# MSP-RFID.net
KiCad netlist of a schematic drawn in Altium Designer
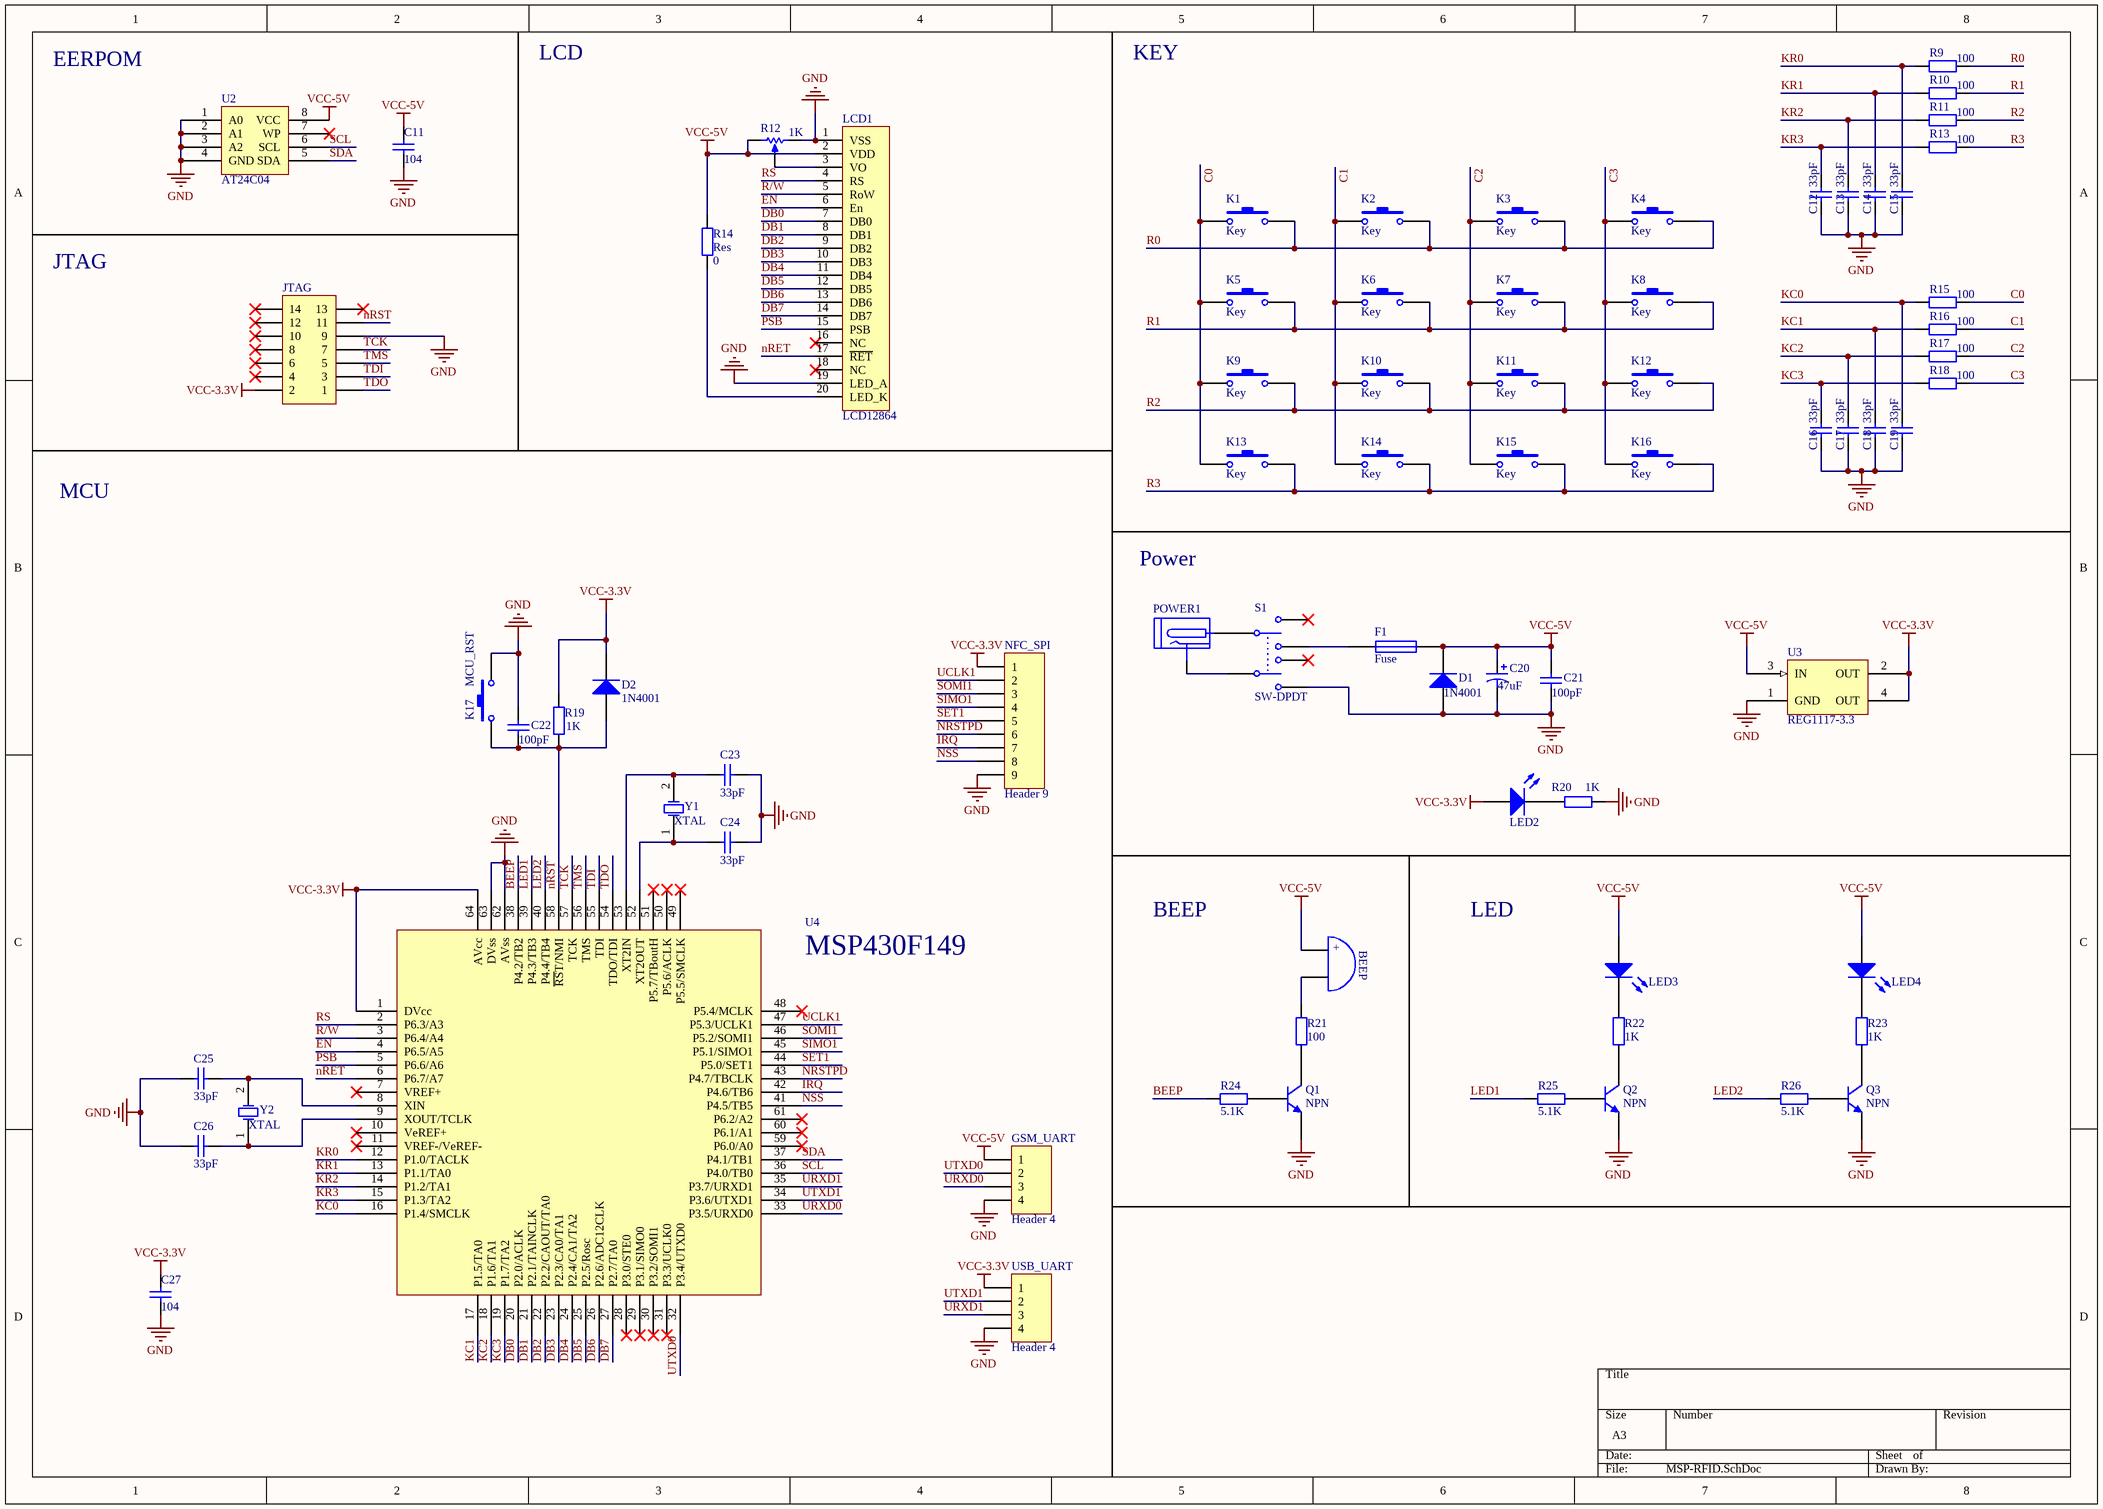
[diagram p0: MSP-RFID.SchDoc]

(export (version "E")
  (design (tool "Eeschema 10.0.6"))
  (components
    (comp (ref "BEEP1") (value "BEEP") (footprint "BEEP") (libsource (lib "common") (part "BEEP")))
    (comp (ref "C11")
      (value "104")
      (footprint "1608[0603]")
      (description "Capacitor")
      (fields (field (name "Comment") "Cap") (field (name "PUBLISHER") "Altium Limited"))
      (libsource (lib "common") (part "Cap"))
    )
    (comp (ref "C12")
      (value "33pF")
      (footprint "1608[0603]")
      (description "Capacitor")
      (fields (field (name "Comment") "Cap") (field (name "PUBLISHER") "Altium Limited"))
      (libsource (lib "common") (part "Cap"))
    )
    (comp (ref "C13")
      (value "33pF")
      (footprint "1608[0603]")
      (description "Capacitor")
      (fields (field (name "Comment") "Cap") (field (name "PUBLISHER") "Altium Limited"))
      (libsource (lib "common") (part "Cap"))
    )
    (comp (ref "C14")
      (value "33pF")
      (footprint "1608[0603]")
      (description "Capacitor")
      (fields (field (name "Comment") "Cap") (field (name "PUBLISHER") "Altium Limited"))
      (libsource (lib "common") (part "Cap"))
    )
    (comp (ref "C15")
      (value "33pF")
      (footprint "1608[0603]")
      (description "Capacitor")
      (fields (field (name "Comment") "Cap") (field (name "PUBLISHER") "Altium Limited"))
      (libsource (lib "common") (part "Cap"))
    )
    (comp (ref "C16")
      (value "33pF")
      (footprint "1608[0603]")
      (description "Capacitor")
      (fields (field (name "Comment") "Cap") (field (name "PUBLISHER") "Altium Limited"))
      (libsource (lib "common") (part "Cap"))
    )
    (comp (ref "C17")
      (value "33pF")
      (footprint "1608[0603]")
      (description "Capacitor")
      (fields (field (name "Comment") "Cap") (field (name "PUBLISHER") "Altium Limited"))
      (libsource (lib "common") (part "Cap"))
    )
    (comp (ref "C18")
      (value "33pF")
      (footprint "1608[0603]")
      (description "Capacitor")
      (fields (field (name "Comment") "Cap") (field (name "PUBLISHER") "Altium Limited"))
      (libsource (lib "common") (part "Cap"))
    )
    (comp (ref "C19")
      (value "33pF")
      (footprint "1608[0603]")
      (description "Capacitor")
      (fields (field (name "Comment") "Cap") (field (name "PUBLISHER") "Altium Limited"))
      (libsource (lib "common") (part "Cap"))
    )
    (comp (ref "C20")
      (value "47uF")
      (footprint "1608[0603] - POL")
      (description "Polarized Capacitor (Axial)")
      (fields (field (name "Comment") "CAP POL") (field (name "PUBLISHER") "Altium Limited"))
      (libsource (lib "common") (part "CAP POL"))
    )
    (comp (ref "C21")
      (value "100pF")
      (footprint "1608[0603]")
      (description "Capacitor")
      (fields (field (name "Comment") "Cap") (field (name "PUBLISHER") "Altium Limited"))
      (libsource (lib "common") (part "Cap"))
    )
    (comp (ref "C22")
      (value "100pF")
      (footprint "1608[0603]")
      (description "Capacitor")
      (fields (field (name "Comment") "Cap") (field (name "PUBLISHER") "Altium Limited"))
      (libsource (lib "common") (part "Cap"))
    )
    (comp (ref "C23")
      (value "33pF")
      (footprint "1608[0603]")
      (description "Capacitor")
      (fields (field (name "Comment") "Cap") (field (name "PUBLISHER") "Altium Limited"))
      (libsource (lib "common") (part "Cap"))
    )
    (comp (ref "C24")
      (value "33pF")
      (footprint "1608[0603]")
      (description "Capacitor")
      (fields (field (name "Comment") "Cap") (field (name "PUBLISHER") "Altium Limited"))
      (libsource (lib "common") (part "Cap"))
    )
    (comp (ref "C25")
      (value "33pF")
      (footprint "1608[0603]")
      (description "Capacitor")
      (fields (field (name "Comment") "Cap") (field (name "PUBLISHER") "Altium Limited"))
      (libsource (lib "common") (part "Cap"))
    )
    (comp (ref "C26")
      (value "33pF")
      (footprint "1608[0603]")
      (description "Capacitor")
      (fields (field (name "Comment") "Cap") (field (name "PUBLISHER") "Altium Limited"))
      (libsource (lib "common") (part "Cap"))
    )
    (comp (ref "C27")
      (value "104")
      (footprint "1608[0603]")
      (description "Capacitor")
      (fields (field (name "Comment") "Cap") (field (name "PUBLISHER") "Altium Limited"))
      (libsource (lib "common") (part "Cap"))
    )
    (comp (ref "D1")
      (value "1N4001")
      (footprint "1608[0603] - POL")
      (description "1 Amp General Purpose Rectifier")
      (fields (field (name "PUBLISHER") "Altium Limited"))
      (libsource (lib "common") (part "Diode 1N4001"))
    )
    (comp (ref "D2")
      (value "1N4001")
      (footprint "1608[0603] - POL")
      (description "1 Amp General Purpose Rectifier")
      (fields (field (name "PUBLISHER") "Altium Limited"))
      (libsource (lib "common") (part "Diode 1N4001"))
    )
    (comp (ref "F1") (value "Fuse") (footprint "1608[0603]") (libsource (lib "common") (part "FUSE1")))
    (comp (ref "GSM_UART")
      (value "Header 4")
      (footprint "HDR1X4")
      (description "Header, 4-Pin")
      (fields (field (name "PUBLISHER") "Altium Limited"))
      (libsource (lib "Miscellaneous Connectors") (part "Header 4"))
    )
    (comp (ref "JTAG")
      (value "Header 7X2H")
      (footprint "HDR2X7H")
      (description "Header, 7-Pin, Dual row, Right Angle")
      (fields (field (name "PUBLISHER") "Altium Limited"))
      (libsource (lib "Miscellaneous Connectors") (part "Header 7X2H"))
    )
    (comp (ref "K1") (value "Key") (footprint "Key-4") (libsource (lib "*") (part "SW-PB")))
    (comp (ref "K2") (value "Key") (footprint "Key-4") (libsource (lib "common") (part "SW-PB")))
    (comp (ref "K3") (value "Key") (footprint "Key-4") (libsource (lib "common") (part "SW-PB")))
    (comp (ref "K4") (value "Key") (footprint "Key-4") (libsource (lib "common") (part "SW-PB")))
    (comp (ref "K5") (value "Key") (footprint "Key-4") (libsource (lib "common") (part "SW-PB")))
    (comp (ref "K6") (value "Key") (footprint "Key-4") (libsource (lib "common") (part "SW-PB")))
    (comp (ref "K7") (value "Key") (footprint "Key-4") (libsource (lib "common") (part "SW-PB")))
    (comp (ref "K8") (value "Key") (footprint "Key-4") (libsource (lib "common") (part "SW-PB")))
    (comp (ref "K9") (value "Key") (footprint "Key-4") (libsource (lib "common") (part "SW-PB")))
    (comp (ref "K10") (value "Key") (footprint "Key-4") (libsource (lib "common") (part "SW-PB")))
    (comp (ref "K11") (value "Key") (footprint "Key-4") (libsource (lib "common") (part "SW-PB")))
    (comp (ref "K12") (value "Key") (footprint "Key-4") (libsource (lib "common") (part "SW-PB")))
    (comp (ref "K13") (value "Key") (footprint "Key-4") (libsource (lib "common") (part "SW-PB")))
    (comp (ref "K14") (value "Key") (footprint "Key-4") (libsource (lib "common") (part "SW-PB")))
    (comp (ref "K15") (value "Key") (footprint "Key-4") (libsource (lib "common") (part "SW-PB")))
    (comp (ref "K16") (value "Key") (footprint "Key-4") (libsource (lib "common") (part "SW-PB")))
    (comp (ref "K17") (value "MCU_RST") (footprint "Key-4") (libsource (lib "common") (part "SW-PB")))
    (comp (ref "LCD1") (value "LCD12864") (footprint "LCD-20PIN") (libsource (lib "*") (part "LCD12864")))
    (comp (ref "LED2") (value "LED") (footprint "2012[0805] - POL") (libsource (lib "common") (part "LED")))
    (comp (ref "LED3") (value "LED") (footprint "1608[0603] - POL") (libsource (lib "common") (part "LED")))
    (comp (ref "LED4") (value "LED") (footprint "1608[0603] - POL") (libsource (lib "common") (part "LED")))
    (comp (ref "NFC_SPI")
      (value "Header 9")
      (footprint "HDR1X9")
      (description "Header, 9-Pin")
      (fields (field (name "PUBLISHER") "Altium Limited"))
      (libsource (lib "Miscellaneous Connectors") (part "Header 9"))
    )
    (comp (ref "POWER1") (value "POWER") (footprint "POWER") (libsource (lib "51ExpBoard") (part "POWER")))
    (comp (ref "Q1") (value "NPN") (footprint "SOT23-3L") (libsource (lib "common") (part "NPN")))
    (comp (ref "Q2") (value "NPN") (footprint "SOT23-3L") (libsource (lib "common") (part "NPN")))
    (comp (ref "Q3") (value "NPN") (footprint "SOT23-3L") (libsource (lib "common") (part "NPN")))
    (comp (ref "R9")
      (value "100")
      (footprint "1608[0603]")
      (description "Resistor")
      (fields (field (name "Comment") "RES") (field (name "PUBLISHER") "Altium Limited"))
      (libsource (lib "common") (part "RES"))
    )
    (comp (ref "R10")
      (value "100")
      (footprint "1608[0603]")
      (description "Resistor")
      (fields (field (name "Comment") "RES") (field (name "PUBLISHER") "Altium Limited"))
      (libsource (lib "common") (part "RES"))
    )
    (comp (ref "R11")
      (value "100")
      (footprint "1608[0603]")
      (description "Resistor")
      (fields (field (name "Comment") "RES") (field (name "PUBLISHER") "Altium Limited"))
      (libsource (lib "common") (part "RES"))
    )
    (comp (ref "R12")
      (value "1K")
      (footprint "VR5")
      (description "Potentiometer")
      (fields (field (name "Comment") "RPot") (field (name "PUBLISHER") "Altium Limited"))
      (libsource (lib "Miscellaneous Devices") (part "RPot"))
    )
    (comp (ref "R13")
      (value "100")
      (footprint "1608[0603]")
      (description "Resistor")
      (fields (field (name "Comment") "RES") (field (name "PUBLISHER") "Altium Limited"))
      (libsource (lib "common") (part "RES"))
    )
    (comp (ref "R14")
      (value "Res")
      (footprint "1608[0603]")
      (description "Resistor")
      (fields (field (name "ALTIUM_VALUE") "0") (field (name "PUBLISHER") "Altium Limited"))
      (libsource (lib "*") (part "RES"))
    )
    (comp (ref "R15")
      (value "100")
      (footprint "1608[0603]")
      (description "Resistor")
      (fields (field (name "Comment") "RES") (field (name "PUBLISHER") "Altium Limited"))
      (libsource (lib "common") (part "RES"))
    )
    (comp (ref "R16")
      (value "100")
      (footprint "1608[0603]")
      (description "Resistor")
      (fields (field (name "Comment") "RES") (field (name "PUBLISHER") "Altium Limited"))
      (libsource (lib "common") (part "RES"))
    )
    (comp (ref "R17")
      (value "100")
      (footprint "1608[0603]")
      (description "Resistor")
      (fields (field (name "Comment") "RES") (field (name "PUBLISHER") "Altium Limited"))
      (libsource (lib "common") (part "RES"))
    )
    (comp (ref "R18")
      (value "100")
      (footprint "1608[0603]")
      (description "Resistor")
      (fields (field (name "Comment") "RES") (field (name "PUBLISHER") "Altium Limited"))
      (libsource (lib "common") (part "RES"))
    )
    (comp (ref "R19")
      (value "1K")
      (footprint "1608[0603]")
      (description "Resistor")
      (fields (field (name "Comment") "Res") (field (name "PUBLISHER") "Altium Limited"))
      (libsource (lib "") (part "RES_2"))
    )
    (comp (ref "R20")
      (value "1K")
      (footprint "1608[0603]")
      (description "Resistor")
      (fields (field (name "Comment") "Res") (field (name "PUBLISHER") "Altium Limited"))
      (libsource (lib "common") (part "RES"))
    )
    (comp (ref "R21")
      (value "100")
      (footprint "1608[0603]")
      (description "Resistor")
      (fields (field (name "Comment") "Res") (field (name "PUBLISHER") "Altium Limited"))
      (libsource (lib "") (part "RES_1"))
    )
    (comp (ref "R22")
      (value "1K")
      (footprint "1608[0603]")
      (description "Resistor")
      (fields (field (name "Comment") "Res") (field (name "PUBLISHER") "Altium Limited"))
      (libsource (lib "") (part "RES_1"))
    )
    (comp (ref "R23")
      (value "1K")
      (footprint "1608[0603]")
      (description "Resistor")
      (fields (field (name "Comment") "Res") (field (name "PUBLISHER") "Altium Limited"))
      (libsource (lib "") (part "RES_1"))
    )
    (comp (ref "R24")
      (value "5.1K")
      (footprint "1608[0603]")
      (description "Resistor")
      (fields (field (name "Comment") "Res") (field (name "PUBLISHER") "Altium Limited"))
      (libsource (lib "common") (part "RES"))
    )
    (comp (ref "R25")
      (value "5.1K")
      (footprint "1608[0603]")
      (description "Resistor")
      (fields (field (name "Comment") "Res") (field (name "PUBLISHER") "Altium Limited"))
      (libsource (lib "common") (part "RES"))
    )
    (comp (ref "R26")
      (value "5.1K")
      (footprint "1608[0603]")
      (description "Resistor")
      (fields (field (name "Comment") "Res") (field (name "PUBLISHER") "Altium Limited"))
      (libsource (lib "common") (part "RES"))
    )
    (comp (ref "S1")
      (value "SW-DPDT")
      (footprint "DPDT-6")
      (description "Double-Pole, Double-Throw Switch")
      (fields (field (name "PUBLISHER") "Altium Limited"))
      (libsource (lib "Miscellaneous Devices") (part "SW-DPDT"))
    )
    (comp (ref "U2")
      (value "AT24C04")
      (footprint "SOIC127P600-8AN")
      (libsource (lib "common") (part "AT24C04"))
    )
    (comp (ref "U3")
      (value "REG1117-3.3")
      (footprint "SOT223")
      (libsource (lib "MYSELF") (part "REG1117-3.3"))
    )
    (comp (ref "U4")
      (value "MSP430F149")
      (footprint "SQFP50P1200X1200-64N")
      (libsource (lib "msp430flash系列") (part "F14X"))
    )
    (comp (ref "USB_UART")
      (value "Header 4")
      (footprint "HDR1X4")
      (description "Header, 4-Pin")
      (fields (field (name "PUBLISHER") "Altium Limited"))
      (libsource (lib "Miscellaneous Connectors") (part "Header 4"))
    )
    (comp (ref "Y1")
      (value "XTAL")
      (footprint "XTAL")
      (description "Crystal Oscillator")
      (fields (field (name "PUBLISHER") "Altium Limited"))
      (libsource (lib "common") (part "XTAL"))
    )
    (comp (ref "Y2")
      (value "XTAL")
      (footprint "XTAL")
      (description "Crystal Oscillator")
      (fields (field (name "PUBLISHER") "Altium Limited"))
      (libsource (lib "common") (part "XTAL"))
    )
  )
  (nets
    (net (code "1") (name "/BEEP") (class "Default")
      (node (ref "R24") (pin "1") (pinfunction "1_1") (pintype "passive"))
      (node (ref "U4") (pin "38") (pinfunction "P4.2/TB2_38") (pintype "power_in"))
    )
    (net (code "2") (name "/C0") (class "Default")
      (node (ref "K1") (pin "1") (pinfunction "1_1") (pintype "passive"))
      (node (ref "K13") (pin "1") (pinfunction "1_1") (pintype "passive"))
      (node (ref "K5") (pin "1") (pinfunction "1_1") (pintype "passive"))
      (node (ref "K9") (pin "1") (pinfunction "1_1") (pintype "passive"))
      (node (ref "R15") (pin "2") (pinfunction "2_2") (pintype "passive"))
    )
    (net (code "3") (name "/C1") (class "Default")
      (node (ref "K10") (pin "1") (pinfunction "1_1") (pintype "passive"))
      (node (ref "K14") (pin "1") (pinfunction "1_1") (pintype "passive"))
      (node (ref "K2") (pin "1") (pinfunction "1_1") (pintype "passive"))
      (node (ref "K6") (pin "1") (pinfunction "1_1") (pintype "passive"))
      (node (ref "R16") (pin "2") (pinfunction "2_2") (pintype "passive"))
    )
    (net (code "4") (name "/C2") (class "Default")
      (node (ref "K11") (pin "1") (pinfunction "1_1") (pintype "passive"))
      (node (ref "K15") (pin "1") (pinfunction "1_1") (pintype "passive"))
      (node (ref "K3") (pin "1") (pinfunction "1_1") (pintype "passive"))
      (node (ref "K7") (pin "1") (pinfunction "1_1") (pintype "passive"))
      (node (ref "R17") (pin "2") (pinfunction "2_2") (pintype "passive"))
    )
    (net (code "5") (name "/C3") (class "Default")
      (node (ref "K12") (pin "1") (pinfunction "1_1") (pintype "passive"))
      (node (ref "K16") (pin "1") (pinfunction "1_1") (pintype "passive"))
      (node (ref "K4") (pin "1") (pinfunction "1_1") (pintype "passive"))
      (node (ref "K8") (pin "1") (pinfunction "1_1") (pintype "passive"))
      (node (ref "R18") (pin "2") (pinfunction "2_2") (pintype "passive"))
    )
    (net (code "6") (name "/DB0") (class "Default")
      (node (ref "LCD1") (pin "7") (pinfunction "DB0_7") (pintype "passive"))
      (node (ref "U4") (pin "20") (pinfunction "P2.0/ACLK_20") (pintype "power_in"))
    )
    (net (code "7") (name "/DB1") (class "Default")
      (node (ref "LCD1") (pin "8") (pinfunction "DB1_8") (pintype "passive"))
      (node (ref "U4") (pin "21") (pinfunction "P2.1/TAINCLK_21") (pintype "power_in"))
    )
    (net (code "8") (name "/DB2") (class "Default")
      (node (ref "LCD1") (pin "9") (pinfunction "DB2_9") (pintype "passive"))
      (node (ref "U4") (pin "22") (pinfunction "P2.2/CAOUT/TA0_22") (pintype "power_in"))
    )
    (net (code "9") (name "/DB3") (class "Default")
      (node (ref "LCD1") (pin "10") (pinfunction "DB3_10") (pintype "passive"))
      (node (ref "U4") (pin "23") (pinfunction "P2.3/CA0/TA1_23") (pintype "power_in"))
    )
    (net (code "10") (name "/DB4") (class "Default")
      (node (ref "LCD1") (pin "11") (pinfunction "DB4_11") (pintype "passive"))
      (node (ref "U4") (pin "24") (pinfunction "P2.4/CA1/TA2_24") (pintype "power_in"))
    )
    (net (code "11") (name "/DB5") (class "Default")
      (node (ref "LCD1") (pin "12") (pinfunction "DB5_12") (pintype "passive"))
      (node (ref "U4") (pin "25") (pinfunction "P2.5/Rosc_25") (pintype "power_in"))
    )
    (net (code "12") (name "/DB6") (class "Default")
      (node (ref "LCD1") (pin "13") (pinfunction "DB6_13") (pintype "passive"))
      (node (ref "U4") (pin "26") (pinfunction "P2.6/ADC12CLK_26") (pintype "power_in"))
    )
    (net (code "13") (name "/DB7") (class "Default")
      (node (ref "LCD1") (pin "14") (pinfunction "DB7_14") (pintype "passive"))
      (node (ref "U4") (pin "27") (pinfunction "P2.7/TA0_27") (pintype "power_in"))
    )
    (net (code "14") (name "/EN") (class "Default")
      (node (ref "LCD1") (pin "6") (pinfunction "En_6") (pintype "passive"))
      (node (ref "U4") (pin "4") (pinfunction "P6.5/A5_4") (pintype "power_in"))
    )
    (net (code "15") (name "/IRQ") (class "Default")
      (node (ref "NFC_SPI") (pin "7") (pinfunction "7_7") (pintype "passive"))
      (node (ref "U4") (pin "42") (pinfunction "P4.6/TB6_42") (pintype "power_in"))
    )
    (net (code "16") (name "/KC0") (class "Default")
      (node (ref "C19") (pin "1") (pinfunction "1_1") (pintype "passive"))
      (node (ref "R15") (pin "1") (pinfunction "1_1") (pintype "passive"))
      (node (ref "U4") (pin "16") (pinfunction "P1.4/SMCLK_16") (pintype "power_in"))
    )
    (net (code "17") (name "/KC1") (class "Default")
      (node (ref "C18") (pin "1") (pinfunction "1_1") (pintype "passive"))
      (node (ref "R16") (pin "1") (pinfunction "1_1") (pintype "passive"))
      (node (ref "U4") (pin "17") (pinfunction "P1.5/TA0_17") (pintype "power_in"))
    )
    (net (code "18") (name "/KC2") (class "Default")
      (node (ref "C17") (pin "1") (pinfunction "1_1") (pintype "passive"))
      (node (ref "R17") (pin "1") (pinfunction "1_1") (pintype "passive"))
      (node (ref "U4") (pin "18") (pinfunction "P1.6/TA1_18") (pintype "power_in"))
    )
    (net (code "19") (name "/KC3") (class "Default")
      (node (ref "C16") (pin "1") (pinfunction "1_1") (pintype "passive"))
      (node (ref "R18") (pin "1") (pinfunction "1_1") (pintype "passive"))
      (node (ref "U4") (pin "19") (pinfunction "P1.7/TA2_19") (pintype "power_in"))
    )
    (net (code "20") (name "/KR0") (class "Default")
      (node (ref "C15") (pin "1") (pinfunction "1_1") (pintype "passive"))
      (node (ref "R9") (pin "1") (pinfunction "1_1") (pintype "passive"))
      (node (ref "U4") (pin "12") (pinfunction "P1.0/TACLK_12") (pintype "power_in"))
    )
    (net (code "21") (name "/KR1") (class "Default")
      (node (ref "C14") (pin "1") (pinfunction "1_1") (pintype "passive"))
      (node (ref "R10") (pin "1") (pinfunction "1_1") (pintype "passive"))
      (node (ref "U4") (pin "13") (pinfunction "P1.1/TA0_13") (pintype "power_in"))
    )
    (net (code "22") (name "/KR2") (class "Default")
      (node (ref "C13") (pin "1") (pinfunction "1_1") (pintype "passive"))
      (node (ref "R11") (pin "1") (pinfunction "1_1") (pintype "passive"))
      (node (ref "U4") (pin "14") (pinfunction "P1.2/TA1_14") (pintype "power_in"))
    )
    (net (code "23") (name "/KR3") (class "Default")
      (node (ref "C12") (pin "1") (pinfunction "1_1") (pintype "passive"))
      (node (ref "R13") (pin "1") (pinfunction "1_1") (pintype "passive"))
      (node (ref "U4") (pin "15") (pinfunction "P1.3/TA2_15") (pintype "power_in"))
    )
    (net (code "24") (name "/LED1") (class "Default")
      (node (ref "R25") (pin "1") (pinfunction "1_1") (pintype "passive"))
      (node (ref "U4") (pin "39") (pinfunction "P4.3/TB3_39") (pintype "power_in"))
    )
    (net (code "25") (name "/LED2") (class "Default")
      (node (ref "R26") (pin "1") (pinfunction "1_1") (pintype "passive"))
      (node (ref "U4") (pin "40") (pinfunction "P4.4/TB4_40") (pintype "power_in"))
    )
    (net (code "26") (name "/NRSTPD") (class "Default")
      (node (ref "NFC_SPI") (pin "6") (pinfunction "6_6") (pintype "passive"))
      (node (ref "U4") (pin "43") (pinfunction "P4.7/TBCLK_43") (pintype "power_in"))
    )
    (net (code "27") (name "/NSS") (class "Default")
      (node (ref "NFC_SPI") (pin "8") (pinfunction "8_8") (pintype "passive"))
      (node (ref "U4") (pin "41") (pinfunction "P4.5/TB5_41") (pintype "power_in"))
    )
    (net (code "28") (name "/PSB") (class "Default")
      (node (ref "LCD1") (pin "15") (pinfunction "PSB_15") (pintype "passive"))
      (node (ref "U4") (pin "5") (pinfunction "P6.6/A6_5") (pintype "power_in"))
    )
    (net (code "29") (name "/R0") (class "Default")
      (node (ref "K1") (pin "2") (pinfunction "2_2") (pintype "passive"))
      (node (ref "K2") (pin "2") (pinfunction "2_2") (pintype "passive"))
      (node (ref "K3") (pin "2") (pinfunction "2_2") (pintype "passive"))
      (node (ref "K4") (pin "2") (pinfunction "2_2") (pintype "passive"))
      (node (ref "R9") (pin "2") (pinfunction "2_2") (pintype "passive"))
    )
    (net (code "30") (name "/R1") (class "Default")
      (node (ref "K5") (pin "2") (pinfunction "2_2") (pintype "passive"))
      (node (ref "K6") (pin "2") (pinfunction "2_2") (pintype "passive"))
      (node (ref "K7") (pin "2") (pinfunction "2_2") (pintype "passive"))
      (node (ref "K8") (pin "2") (pinfunction "2_2") (pintype "passive"))
      (node (ref "R10") (pin "2") (pinfunction "2_2") (pintype "passive"))
    )
    (net (code "31") (name "/R2") (class "Default")
      (node (ref "K10") (pin "2") (pinfunction "2_2") (pintype "passive"))
      (node (ref "K11") (pin "2") (pinfunction "2_2") (pintype "passive"))
      (node (ref "K12") (pin "2") (pinfunction "2_2") (pintype "passive"))
      (node (ref "K9") (pin "2") (pinfunction "2_2") (pintype "passive"))
      (node (ref "R11") (pin "2") (pinfunction "2_2") (pintype "passive"))
    )
    (net (code "32") (name "/R3") (class "Default")
      (node (ref "K13") (pin "2") (pinfunction "2_2") (pintype "passive"))
      (node (ref "K14") (pin "2") (pinfunction "2_2") (pintype "passive"))
      (node (ref "K15") (pin "2") (pinfunction "2_2") (pintype "passive"))
      (node (ref "K16") (pin "2") (pinfunction "2_2") (pintype "passive"))
      (node (ref "R13") (pin "2") (pinfunction "2_2") (pintype "passive"))
    )
    (net (code "33") (name "/RS") (class "Default")
      (node (ref "LCD1") (pin "4") (pinfunction "RS_4") (pintype "passive"))
      (node (ref "U4") (pin "2") (pinfunction "P6.3/A3_2") (pintype "power_in"))
    )
    (net (code "34") (name "/R{slash}W") (class "Default")
      (node (ref "LCD1") (pin "5") (pinfunction "RoW_5") (pintype "passive"))
      (node (ref "U4") (pin "3") (pinfunction "P6.4/A4_3") (pintype "power_in"))
    )
    (net (code "35") (name "/SCL") (class "Default")
      (node (ref "U2") (pin "6") (pinfunction "SCL_6") (pintype "passive"))
      (node (ref "U4") (pin "36") (pinfunction "P4.0/TB0_36") (pintype "power_in"))
    )
    (net (code "36") (name "/SDA") (class "Default")
      (node (ref "U2") (pin "5") (pinfunction "SDA_5") (pintype "passive"))
      (node (ref "U4") (pin "37") (pinfunction "P4.1/TB1_37") (pintype "power_in"))
    )
    (net (code "37") (name "/SET1") (class "Default")
      (node (ref "NFC_SPI") (pin "5") (pinfunction "5_5") (pintype "passive"))
      (node (ref "U4") (pin "44") (pinfunction "P5.0/SET1_44") (pintype "power_in"))
    )
    (net (code "38") (name "/SIMO1") (class "Default")
      (node (ref "NFC_SPI") (pin "4") (pinfunction "4_4") (pintype "passive"))
      (node (ref "U4") (pin "45") (pinfunction "P5.1/SIMO1_45") (pintype "power_in"))
    )
    (net (code "39") (name "/SOMI1") (class "Default")
      (node (ref "NFC_SPI") (pin "3") (pinfunction "3_3") (pintype "passive"))
      (node (ref "U4") (pin "46") (pinfunction "P5.2/SOMI1_46") (pintype "power_in"))
    )
    (net (code "40") (name "/TCK") (class "Default")
      (node (ref "JTAG") (pin "7") (pinfunction "7_7") (pintype "passive"))
      (node (ref "U4") (pin "57") (pinfunction "TCK_57") (pintype "power_in"))
    )
    (net (code "41") (name "/TDI") (class "Default")
      (node (ref "JTAG") (pin "3") (pinfunction "3_3") (pintype "passive"))
      (node (ref "U4") (pin "55") (pinfunction "TDI_55") (pintype "power_in"))
    )
    (net (code "42") (name "/TDO") (class "Default")
      (node (ref "JTAG") (pin "1") (pinfunction "1_1") (pintype "passive"))
      (node (ref "U4") (pin "54") (pinfunction "TDO/TDI_54") (pintype "power_in"))
    )
    (net (code "43") (name "/TMS") (class "Default")
      (node (ref "JTAG") (pin "5") (pinfunction "5_5") (pintype "passive"))
      (node (ref "U4") (pin "56") (pinfunction "TMS_56") (pintype "power_in"))
    )
    (net (code "44") (name "/UCLK1") (class "Default")
      (node (ref "NFC_SPI") (pin "2") (pinfunction "2_2") (pintype "passive"))
      (node (ref "U4") (pin "47") (pinfunction "P5.3/UCLK1_47") (pintype "power_in"))
    )
    (net (code "45") (name "/URXD0") (class "Default")
      (node (ref "GSM_UART") (pin "3") (pinfunction "3_3") (pintype "passive"))
      (node (ref "U4") (pin "33") (pinfunction "P3.5/URXD0_33") (pintype "power_in"))
    )
    (net (code "46") (name "/URXD1") (class "Default")
      (node (ref "U4") (pin "35") (pinfunction "P3.7/URXD1_35") (pintype "power_in"))
      (node (ref "USB_UART") (pin "3") (pinfunction "3_3") (pintype "passive"))
    )
    (net (code "47") (name "/UTXD0") (class "Default")
      (node (ref "GSM_UART") (pin "2") (pinfunction "2_2") (pintype "passive"))
      (node (ref "U4") (pin "32") (pinfunction "P3.4/UTXD0_32") (pintype "power_in"))
    )
    (net (code "48") (name "/UTXD1") (class "Default")
      (node (ref "U4") (pin "34") (pinfunction "P3.6/UTXD1_34") (pintype "power_in"))
      (node (ref "USB_UART") (pin "2") (pinfunction "2_2") (pintype "passive"))
    )
    (net (code "49") (name "/nRET") (class "Default")
      (node (ref "LCD1") (pin "17") (pinfunction "~{RET}_17") (pintype "passive"))
      (node (ref "U4") (pin "6") (pinfunction "P6.7/A7_6") (pintype "power_in"))
    )
    (net (code "50") (name "/nRST") (class "Default")
      (node (ref "C22") (pin "1") (pinfunction "1_1") (pintype "passive"))
      (node (ref "D2") (pin "1") (pinfunction "A_1") (pintype "passive"))
      (node (ref "JTAG") (pin "11") (pinfunction "11_11") (pintype "passive"))
      (node (ref "K17") (pin "1") (pinfunction "1_1") (pintype "passive"))
      (node (ref "R19") (pin "1") (pinfunction "1_1") (pintype "passive"))
      (node (ref "U4") (pin "58") (pinfunction "~{RS}T/NMI_58") (pintype "power_in"))
    )
    (net (code "51") (name "GND") (class "Default")
      (node (ref "C11") (pin "1") (pinfunction "1_1") (pintype "passive"))
      (node (ref "C12") (pin "2") (pinfunction "2_2") (pintype "passive"))
      (node (ref "C13") (pin "2") (pinfunction "2_2") (pintype "passive"))
      (node (ref "C14") (pin "2") (pinfunction "2_2") (pintype "passive"))
      (node (ref "C15") (pin "2") (pinfunction "2_2") (pintype "passive"))
      (node (ref "C16") (pin "2") (pinfunction "2_2") (pintype "passive"))
      (node (ref "C17") (pin "2") (pinfunction "2_2") (pintype "passive"))
      (node (ref "C18") (pin "2") (pinfunction "2_2") (pintype "passive"))
      (node (ref "C19") (pin "2") (pinfunction "2_2") (pintype "passive"))
      (node (ref "C20") (pin "2") (pinfunction "2_2") (pintype "passive"))
      (node (ref "C21") (pin "1") (pinfunction "1_1") (pintype "passive"))
      (node (ref "C22") (pin "2") (pinfunction "2_2") (pintype "passive"))
      (node (ref "C23") (pin "1") (pinfunction "1_1") (pintype "passive"))
      (node (ref "C24") (pin "1") (pinfunction "1_1") (pintype "passive"))
      (node (ref "C25") (pin "2") (pinfunction "2_2") (pintype "passive"))
      (node (ref "C26") (pin "2") (pinfunction "2_2") (pintype "passive"))
      (node (ref "C27") (pin "1") (pinfunction "1_1") (pintype "passive"))
      (node (ref "D1") (pin "1") (pinfunction "A_1") (pintype "passive"))
      (node (ref "GSM_UART") (pin "4") (pinfunction "4_4") (pintype "passive"))
      (node (ref "JTAG") (pin "9") (pinfunction "9_9") (pintype "passive"))
      (node (ref "K17") (pin "2") (pinfunction "2_2") (pintype "passive"))
      (node (ref "LCD1") (pin "1") (pinfunction "VSS_1") (pintype "passive"))
      (node (ref "LCD1") (pin "19") (pinfunction "LED_A_19") (pintype "passive"))
      (node (ref "NFC_SPI") (pin "9") (pinfunction "9_9") (pintype "passive"))
      (node (ref "Q1") (pin "3") (pinfunction "E_3") (pintype "passive"))
      (node (ref "Q2") (pin "3") (pinfunction "E_3") (pintype "passive"))
      (node (ref "Q3") (pin "3") (pinfunction "E_3") (pintype "passive"))
      (node (ref "R12") (pin "2") (pinfunction "BOT_2") (pintype "passive"))
      (node (ref "R20") (pin "2") (pinfunction "2_2") (pintype "passive"))
      (node (ref "S1") (pin "6") (pinfunction "6_6") (pintype "passive"))
      (node (ref "U2") (pin "1") (pinfunction "A0_1") (pintype "passive"))
      (node (ref "U2") (pin "2") (pinfunction "A1_2") (pintype "passive"))
      (node (ref "U2") (pin "3") (pinfunction "A2_3") (pintype "passive"))
      (node (ref "U2") (pin "4") (pinfunction "GND_4") (pintype "passive"))
      (node (ref "U3") (pin "1") (pinfunction "GND_1") (pintype "passive"))
      (node (ref "U4") (pin "62") (pinfunction "AVss_62") (pintype "power_in"))
      (node (ref "U4") (pin "63") (pinfunction "DVss_63") (pintype "power_in"))
      (node (ref "USB_UART") (pin "4") (pinfunction "4_4") (pintype "passive"))
    )
    (net (code "52") (name "Net-(BEEP1-A)") (class "Default")
      (node (ref "BEEP1") (pin "2") (pinfunction "A_2") (pintype "passive"))
      (node (ref "R21") (pin "1") (pinfunction "1_1") (pintype "passive"))
    )
    (net (code "53") (name "Net-(F1-Pad1)") (class "Default")
      (node (ref "F1") (pin "1") (pinfunction "1_1") (pintype "passive"))
      (node (ref "S1") (pin "3") (pinfunction "3_3") (pintype "passive"))
    )
    (net (code "54") (name "Net-(LCD1-LED_K)") (class "Default")
      (node (ref "LCD1") (pin "20") (pinfunction "LED_K_20") (pintype "passive"))
      (node (ref "R14") (pin "1") (pinfunction "1_1") (pintype "passive"))
    )
    (net (code "55") (name "Net-(LCD1-VO)") (class "Default")
      (node (ref "LCD1") (pin "3") (pinfunction "VO_3") (pintype "passive"))
      (node (ref "R12") (pin "3") (pinfunction "TAP_3") (pintype "passive"))
    )
    (net (code "56") (name "Net-(LED2-K)") (class "Default")
      (node (ref "LED2") (pin "2") (pinfunction "K_2") (pintype "passive"))
      (node (ref "R20") (pin "1") (pinfunction "1_1") (pintype "passive"))
    )
    (net (code "57") (name "Net-(LED3-K)") (class "Default")
      (node (ref "LED3") (pin "2") (pinfunction "K_2") (pintype "passive"))
      (node (ref "R22") (pin "1") (pinfunction "1_1") (pintype "passive"))
    )
    (net (code "58") (name "Net-(LED4-K)") (class "Default")
      (node (ref "LED4") (pin "2") (pinfunction "K_2") (pintype "passive"))
      (node (ref "R23") (pin "1") (pinfunction "1_1") (pintype "passive"))
    )
    (net (code "59") (name "Net-(POWER1-Pad1)") (class "Default")
      (node (ref "POWER1") (pin "1") (pinfunction "1_1") (pintype "power_in"))
      (node (ref "S1") (pin "1") (pinfunction "1_1") (pintype "passive"))
    )
    (net (code "60") (name "Net-(POWER1-Pad2)") (class "Default")
      (node (ref "POWER1") (pin "2") (pinfunction "2_2") (pintype "power_in"))
      (node (ref "S1") (pin "4") (pinfunction "4_4") (pintype "passive"))
    )
    (net (code "61") (name "Net-(Q1-B)") (class "Default")
      (node (ref "Q1") (pin "2") (pinfunction "B_2") (pintype "passive"))
      (node (ref "R24") (pin "2") (pinfunction "2_2") (pintype "passive"))
    )
    (net (code "62") (name "Net-(Q1-C)") (class "Default")
      (node (ref "Q1") (pin "1") (pinfunction "C_1") (pintype "passive"))
      (node (ref "R21") (pin "2") (pinfunction "2_2") (pintype "passive"))
    )
    (net (code "63") (name "Net-(Q2-B)") (class "Default")
      (node (ref "Q2") (pin "2") (pinfunction "B_2") (pintype "passive"))
      (node (ref "R25") (pin "2") (pinfunction "2_2") (pintype "passive"))
    )
    (net (code "64") (name "Net-(Q2-C)") (class "Default")
      (node (ref "Q2") (pin "1") (pinfunction "C_1") (pintype "passive"))
      (node (ref "R22") (pin "2") (pinfunction "2_2") (pintype "passive"))
    )
    (net (code "65") (name "Net-(Q3-B)") (class "Default")
      (node (ref "Q3") (pin "2") (pinfunction "B_2") (pintype "passive"))
      (node (ref "R26") (pin "2") (pinfunction "2_2") (pintype "passive"))
    )
    (net (code "66") (name "Net-(Q3-C)") (class "Default")
      (node (ref "Q3") (pin "1") (pinfunction "C_1") (pintype "passive"))
      (node (ref "R23") (pin "2") (pinfunction "2_2") (pintype "passive"))
    )
    (net (code "67") (name "Net-(U4-XIN)") (class "Default")
      (node (ref "C25") (pin "1") (pinfunction "1_1") (pintype "passive"))
      (node (ref "U4") (pin "8") (pinfunction "XIN_8") (pintype "power_in"))
      (node (ref "Y2") (pin "2") (pinfunction "OSC2_2") (pintype "passive"))
    )
    (net (code "68") (name "Net-(U4-XOUT{slash}TCLK)") (class "Default")
      (node (ref "C26") (pin "1") (pinfunction "1_1") (pintype "passive"))
      (node (ref "U4") (pin "9") (pinfunction "XOUT/TCLK_9") (pintype "power_in"))
      (node (ref "Y2") (pin "1") (pinfunction "OSC1_1") (pintype "passive"))
    )
    (net (code "69") (name "Net-(U4-XT2IN)") (class "Default")
      (node (ref "C23") (pin "2") (pinfunction "2_2") (pintype "passive"))
      (node (ref "U4") (pin "53") (pinfunction "XT2IN_53") (pintype "power_in"))
      (node (ref "Y1") (pin "2") (pinfunction "OSC2_2") (pintype "passive"))
    )
    (net (code "70") (name "Net-(U4-XT2OUT)") (class "Default")
      (node (ref "C24") (pin "2") (pinfunction "2_2") (pintype "passive"))
      (node (ref "U4") (pin "52") (pinfunction "XT2OUT_52") (pintype "power_in"))
      (node (ref "Y1") (pin "1") (pinfunction "OSC1_1") (pintype "passive"))
    )
    (net (code "71") (name "VCC-3.3V") (class "Default")
      (node (ref "C27") (pin "2") (pinfunction "2_2") (pintype "passive"))
      (node (ref "D2") (pin "2") (pinfunction "K_2") (pintype "passive"))
      (node (ref "JTAG") (pin "2") (pinfunction "2_2") (pintype "passive"))
      (node (ref "LED2") (pin "1") (pinfunction "A_1") (pintype "passive"))
      (node (ref "NFC_SPI") (pin "1") (pinfunction "1_1") (pintype "passive"))
      (node (ref "R19") (pin "2") (pinfunction "2_2") (pintype "passive"))
      (node (ref "U3") (pin "2") (pinfunction "OUT_2") (pintype "power_in"))
      (node (ref "U3") (pin "4") (pinfunction "OUT_4") (pintype "power_in"))
      (node (ref "U4") (pin "1") (pinfunction "DVcc_1") (pintype "power_in"))
      (node (ref "U4") (pin "64") (pinfunction "AVcc_64") (pintype "power_in"))
      (node (ref "USB_UART") (pin "1") (pinfunction "1_1") (pintype "passive"))
    )
    (net (code "72") (name "VCC-5V") (class "Default")
      (node (ref "BEEP1") (pin "1") (pinfunction "B_1") (pintype "passive"))
      (node (ref "C11") (pin "2") (pinfunction "2_2") (pintype "passive"))
      (node (ref "C20") (pin "1") (pinfunction "1_1") (pintype "passive"))
      (node (ref "C21") (pin "2") (pinfunction "2_2") (pintype "passive"))
      (node (ref "D1") (pin "2") (pinfunction "K_2") (pintype "passive"))
      (node (ref "F1") (pin "2") (pinfunction "2_2") (pintype "passive"))
      (node (ref "GSM_UART") (pin "1") (pinfunction "1_1") (pintype "passive"))
      (node (ref "LCD1") (pin "2") (pinfunction "VDD_2") (pintype "passive"))
      (node (ref "LED3") (pin "1") (pinfunction "A_1") (pintype "passive"))
      (node (ref "LED4") (pin "1") (pinfunction "A_1") (pintype "passive"))
      (node (ref "R12") (pin "1") (pinfunction "TOP_1") (pintype "passive"))
      (node (ref "R14") (pin "2") (pinfunction "2_2") (pintype "passive"))
      (node (ref "U2") (pin "8") (pinfunction "VCC_8") (pintype "passive"))
      (node (ref "U3") (pin "3") (pinfunction "IN_3") (pintype "input"))
    )
    (net (code "73") (name "unconnected-(JTAG-Pad4)") (class "Default")
      (node (ref "JTAG") (pin "4") (pinfunction "4_4") (pintype "passive+no_connect"))
    )
    (net (code "74") (name "unconnected-(JTAG-Pad6)") (class "Default")
      (node (ref "JTAG") (pin "6") (pinfunction "6_6") (pintype "passive+no_connect"))
    )
    (net (code "75") (name "unconnected-(JTAG-Pad8)") (class "Default")
      (node (ref "JTAG") (pin "8") (pinfunction "8_8") (pintype "passive+no_connect"))
    )
    (net (code "76") (name "unconnected-(JTAG-Pad10)") (class "Default")
      (node (ref "JTAG") (pin "10") (pinfunction "10_10") (pintype "passive+no_connect"))
    )
    (net (code "77") (name "unconnected-(JTAG-Pad12)") (class "Default")
      (node (ref "JTAG") (pin "12") (pinfunction "12_12") (pintype "passive+no_connect"))
    )
    (net (code "78") (name "unconnected-(JTAG-Pad13)") (class "Default")
      (node (ref "JTAG") (pin "13") (pinfunction "13_13") (pintype "passive+no_connect"))
    )
    (net (code "79") (name "unconnected-(JTAG-Pad14)") (class "Default")
      (node (ref "JTAG") (pin "14") (pinfunction "14_14") (pintype "passive+no_connect"))
    )
    (net (code "80") (name "unconnected-(LCD1-NC-Pad16)") (class "Default")
      (node (ref "LCD1") (pin "16") (pinfunction "NC_16") (pintype "passive+no_connect"))
    )
    (net (code "81") (name "unconnected-(LCD1-NC-Pad18)") (class "Default")
      (node (ref "LCD1") (pin "18") (pinfunction "NC_18") (pintype "passive+no_connect"))
    )
    (net (code "82") (name "unconnected-(S1-Pad2)") (class "Default")
      (node (ref "S1") (pin "2") (pinfunction "2_2") (pintype "passive+no_connect"))
    )
    (net (code "83") (name "unconnected-(S1-Pad5)") (class "Default")
      (node (ref "S1") (pin "5") (pinfunction "5_5") (pintype "passive+no_connect"))
    )
    (net (code "84") (name "unconnected-(U2-WP-Pad7)") (class "Default")
      (node (ref "U2") (pin "7") (pinfunction "WP_7") (pintype "passive+no_connect"))
    )
    (net (code "85") (name "unconnected-(U4-P3.0{slash}STE0-Pad28)") (class "Default")
      (node (ref "U4") (pin "28") (pinfunction "P3.0/STE0_28") (pintype "power_in+no_connect"))
    )
    (net (code "86") (name "unconnected-(U4-P3.1{slash}SIMO0-Pad29)") (class "Default")
      (node (ref "U4") (pin "29") (pinfunction "P3.1/SIMO0_29") (pintype "power_in+no_connect"))
    )
    (net (code "87") (name "unconnected-(U4-P3.2{slash}SOMI1-Pad30)") (class "Default")
      (node (ref "U4") (pin "30") (pinfunction "P3.2/SOMI1_30") (pintype "power_in+no_connect"))
    )
    (net (code "88") (name "unconnected-(U4-P3.3{slash}UCLK0-Pad31)") (class "Default")
      (node (ref "U4") (pin "31") (pinfunction "P3.3/UCLK0_31") (pintype "power_in+no_connect"))
    )
    (net (code "89") (name "unconnected-(U4-P5.4{slash}MCLK-Pad48)") (class "Default")
      (node (ref "U4") (pin "48") (pinfunction "P5.4/MCLK_48") (pintype "power_in+no_connect"))
    )
    (net (code "90") (name "unconnected-(U4-P5.5{slash}SMCLK-Pad49)") (class "Default")
      (node (ref "U4") (pin "49") (pinfunction "P5.5/SMCLK_49") (pintype "power_in+no_connect"))
    )
    (net (code "91") (name "unconnected-(U4-P5.6{slash}ACLK-Pad50)") (class "Default")
      (node (ref "U4") (pin "50") (pinfunction "P5.6/ACLK_50") (pintype "power_in+no_connect"))
    )
    (net (code "92") (name "unconnected-(U4-P5.7{slash}TBoutH-Pad51)") (class "Default")
      (node (ref "U4") (pin "51") (pinfunction "P5.7/TBoutH_51") (pintype "power_in+no_connect"))
    )
    (net (code "93") (name "unconnected-(U4-P6.0{slash}A0-Pad59)") (class "Default")
      (node (ref "U4") (pin "59") (pinfunction "P6.0/A0_59") (pintype "power_in+no_connect"))
    )
    (net (code "94") (name "unconnected-(U4-P6.1{slash}A1-Pad60)") (class "Default")
      (node (ref "U4") (pin "60") (pinfunction "P6.1/A1_60") (pintype "power_in+no_connect"))
    )
    (net (code "95") (name "unconnected-(U4-P6.2{slash}A2-Pad61)") (class "Default")
      (node (ref "U4") (pin "61") (pinfunction "P6.2/A2_61") (pintype "power_in+no_connect"))
    )
    (net (code "96") (name "unconnected-(U4-VREF+-Pad7)") (class "Default")
      (node (ref "U4") (pin "7") (pinfunction "VREF+_7") (pintype "power_in+no_connect"))
    )
    (net (code "97") (name "unconnected-(U4-VREF-{slash}VeREF--Pad11)") (class "Default")
      (node (ref "U4") (pin "11") (pinfunction "VREF-/VeREF-_11") (pintype "power_in+no_connect"))
    )
    (net (code "98") (name "unconnected-(U4-VeREF+-Pad10)") (class "Default")
      (node (ref "U4") (pin "10") (pinfunction "VeREF+_10") (pintype "power_in+no_connect"))
    )
  )
)
